# StepperDriverV2.net
KiCad netlist of a schematic drawn in Altium Designer
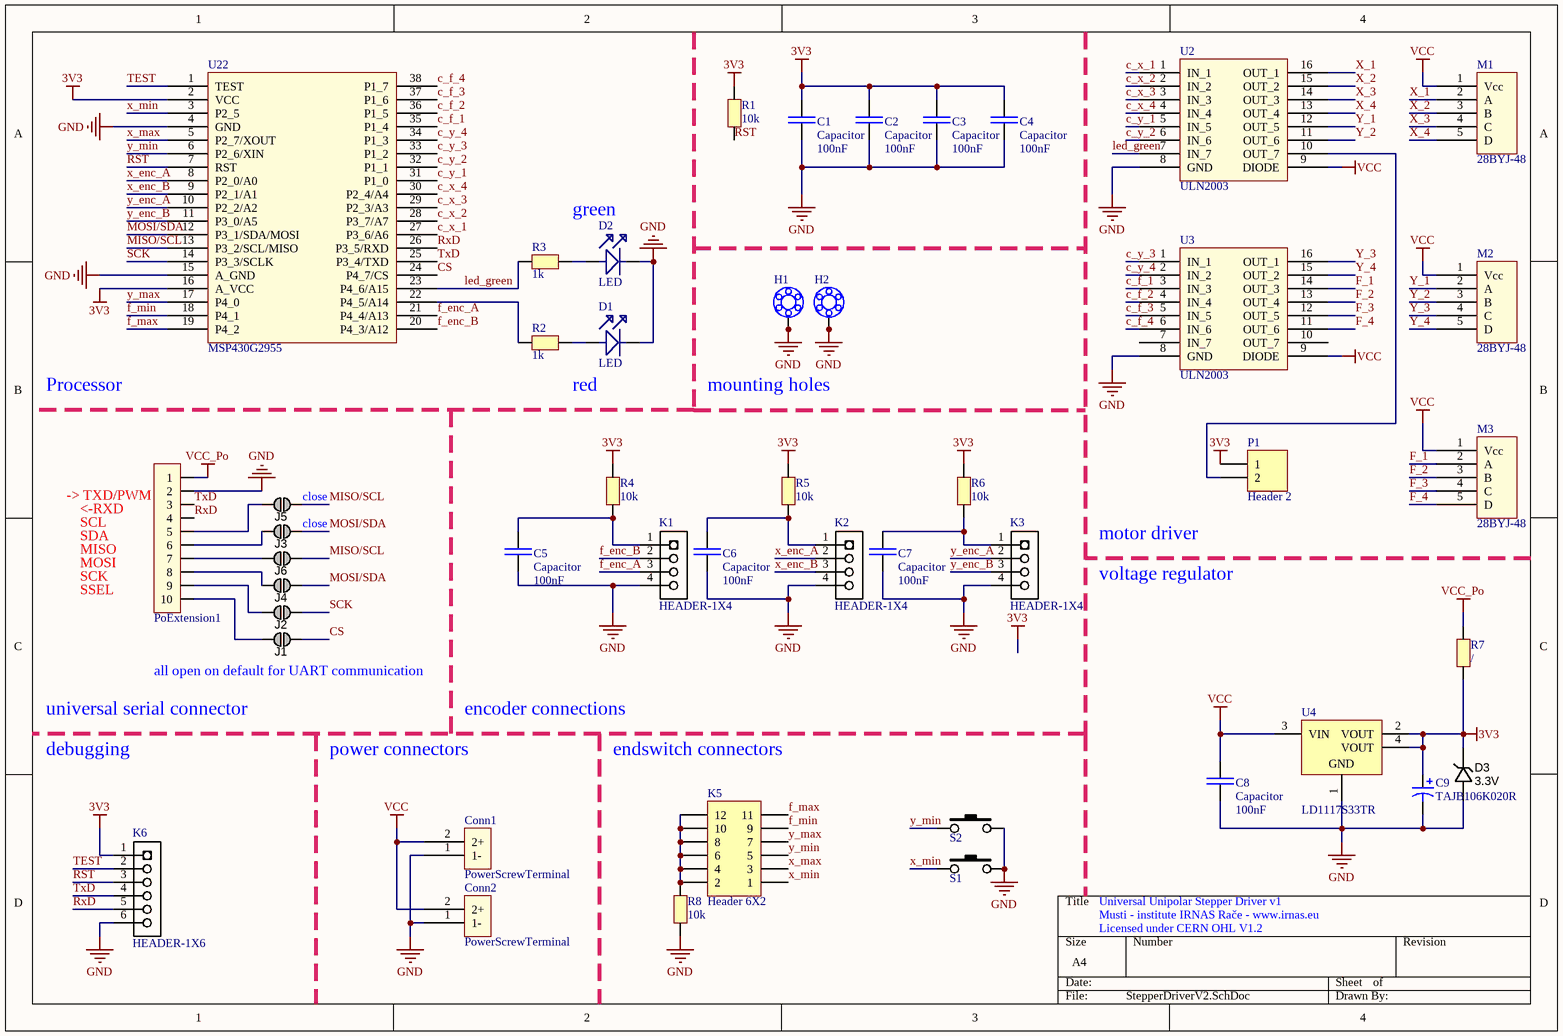
[diagram p0: StepperDriverV2.SchDoc]

(export (version "E")
  (design (tool "Eeschema 10.0.6"))
  (components
    (comp (ref "C1")
      (value "Capacitor")
      (footprint "0603")
      (description "General capacitor")
      (fields (field (name "ALTIUM_VALUE") "100nF"))
      (libsource (lib "GeneralComponents") (part "Capacitor"))
    )
    (comp (ref "C2")
      (value "Capacitor")
      (footprint "0603")
      (description "General capacitor")
      (fields (field (name "ALTIUM_VALUE") "100nF"))
      (libsource (lib "GeneralComponents") (part "Capacitor"))
    )
    (comp (ref "C3")
      (value "Capacitor")
      (footprint "0603")
      (description "General capacitor")
      (fields (field (name "ALTIUM_VALUE") "100nF"))
      (libsource (lib "GeneralComponents") (part "Capacitor"))
    )
    (comp (ref "C4")
      (value "Capacitor")
      (footprint "0603")
      (description "General capacitor")
      (fields (field (name "ALTIUM_VALUE") "100nF"))
      (libsource (lib "GeneralComponents") (part "Capacitor"))
    )
    (comp (ref "C5")
      (value "Capacitor")
      (footprint "0603")
      (description "General capacitor")
      (fields (field (name "ALTIUM_VALUE") "100nF"))
      (libsource (lib "GeneralComponents") (part "Capacitor"))
    )
    (comp (ref "C6")
      (value "Capacitor")
      (footprint "0603")
      (description "General capacitor")
      (fields (field (name "ALTIUM_VALUE") "100nF"))
      (libsource (lib "GeneralComponents") (part "Capacitor"))
    )
    (comp (ref "C7")
      (value "Capacitor")
      (footprint "0603")
      (description "General capacitor")
      (fields (field (name "ALTIUM_VALUE") "100nF"))
      (libsource (lib "GeneralComponents") (part "Capacitor"))
    )
    (comp (ref "C8")
      (value "Capacitor")
      (footprint "0603")
      (description "General capacitor")
      (fields (field (name "ALTIUM_VALUE") "100nF"))
      (libsource (lib "GeneralComponents") (part "Capacitor"))
    )
    (comp (ref "C9")
      (value "TAJB106K020R")
      (footprint "AVX-CAPC3528_V")
      (description "Capacitor, Tantalum, 10uF 10% 20V MCCT-B (3528)")
      (fields (field (name "MANUFACTURER") "AVX") (field (name "TOLERANCE") "10%"))
      (libsource (lib "Altium Content Vault") (part "CMP-0279-00001-1"))
    )
    (comp (ref "Conn1")
      (value "PowerScrewTerminal")
      (footprint "MKDSN 2,5/ 2-5,08 and powercon")
      (libsource (lib "GeneralComponents") (part "PowerScrewTerminal"))
    )
    (comp (ref "Conn2")
      (value "PowerScrewTerminal")
      (footprint "MKDSN 2,5/ 2-5,08 and powercon")
      (libsource (lib "GeneralComponents") (part "PowerScrewTerminal"))
    )
    (comp (ref "D1")
      (value "LED")
      (footprint "RESC2012X06N")
      (description "LED diode")
      (libsource (lib "GeneralComponents") (part "LED"))
    )
    (comp (ref "D2")
      (value "LED")
      (footprint "RESC2012X06N")
      (description "LED diode")
      (libsource (lib "GeneralComponents") (part "LED"))
    )
    (comp (ref "D3")
      (value "3.3V")
      (footprint "SOD323")
      (description "Diode Zener SMD 3.3V 200mW SOD-323")
      (fields (field (name "TOLERANCE") "±3%"))
      (libsource (lib "Misc") (part "DIODE_ZENER_3V3_SOD323"))
    )
    (comp (ref "H1")
      (value "M")
      (footprint "MOUNTING")
      (description "MOUNTING HOLE - NON INSTALLABLE")
      (libsource (lib "vh_altium_library") (part "MOUNTING"))
    )
    (comp (ref "H2")
      (value "M")
      (footprint "MOUNTING")
      (description "MOUNTING HOLE - NON INSTALLABLE")
      (libsource (lib "vh_altium_library") (part "MOUNTING"))
    )
    (comp (ref "J1")
      (value "Jumper")
      (footprint "JUMP1")
      (description "SMD jumper")
      (libsource (lib "Misc") (part "JUMP1"))
    )
    (comp (ref "J2")
      (value "Jumper")
      (footprint "JUMP1")
      (description "SMD jumper")
      (libsource (lib "Misc") (part "JUMP1"))
    )
    (comp (ref "J3")
      (value "Jumper")
      (footprint "JUMP1")
      (description "SMD jumper")
      (libsource (lib "Misc") (part "JUMP1"))
    )
    (comp (ref "J4")
      (value "Jumper")
      (footprint "JUMP1")
      (description "SMD jumper")
      (libsource (lib "Misc") (part "JUMP1"))
    )
    (comp (ref "J5")
      (value "Jumper")
      (footprint "JUMP1")
      (description "SMD jumper")
      (libsource (lib "Misc") (part "JUMP1"))
    )
    (comp (ref "J6")
      (value "Jumper")
      (footprint "JUMP1")
      (description "SMD jumper")
      (libsource (lib "Misc") (part "JUMP1"))
    )
    (comp (ref "K1")
      (value "HEADER-1X4")
      (footprint "HEADER-1X4")
      (libsource (lib "vh_altium_library") (part "HEADER-1X4"))
    )
    (comp (ref "K2")
      (value "HEADER-1X4")
      (footprint "HEADER-1X4")
      (libsource (lib "vh_altium_library") (part "HEADER-1X4"))
    )
    (comp (ref "K3")
      (value "HEADER-1X4")
      (footprint "HEADER-1X4")
      (libsource (lib "vh_altium_library") (part "HEADER-1X4"))
    )
    (comp (ref "K5")
      (value "Header 6X2")
      (footprint "HDR2X6")
      (description "Header, 6-Pin, Dual row")
      (fields (field (name "PUBLISHER") "Altium Limited"))
      (libsource (lib "Miscellaneous Connectors") (part "Header 6X2"))
    )
    (comp (ref "K6")
      (value "HEADER-1X6")
      (footprint "HEADER-1X6")
      (libsource (lib "vh_altium_library") (part "HEADER-1X6"))
    )
    (comp (ref "M1")
      (value "28BYJ-48")
      (footprint "XHP-5")
      (description "Stepper motor")
      (libsource (lib "GeneralComponents") (part "28BYJ-48"))
    )
    (comp (ref "M2")
      (value "28BYJ-48")
      (footprint "XHP-5")
      (description "Stepper motor")
      (libsource (lib "GeneralComponents") (part "28BYJ-48"))
    )
    (comp (ref "M3")
      (value "28BYJ-48")
      (footprint "XHP-5")
      (description "Stepper motor")
      (libsource (lib "GeneralComponents") (part "28BYJ-48"))
    )
    (comp (ref "P1")
      (value "Header 2")
      (footprint "HDR1X2")
      (description "Header, 2-Pin")
      (fields (field (name "PUBLISHER") "Altium Limited"))
      (libsource (lib "Miscellaneous Connectors") (part "Header 2"))
    )
    (comp (ref "PoExtension1")
      (value "~")
      (footprint "BorisMicroMatch:8-188275-0")
      (description "Micro-Match female PCB connector 10 Positions THT")
      (libsource (lib "BorisMicroMatch") (part "1-215079-0"))
    )
    (comp (ref "R1")
      (value "10k")
      (footprint "0603")
      (description "Resistor 0805 smd")
      (libsource (lib "GeneralComponents") (part "Resistor"))
    )
    (comp (ref "R2")
      (value "1k")
      (footprint "0603")
      (description "Resistor 0805 smd")
      (libsource (lib "") (part "Resistor_1"))
    )
    (comp (ref "R3")
      (value "1k")
      (footprint "0603")
      (description "Resistor 0805 smd")
      (libsource (lib "") (part "Resistor_1"))
    )
    (comp (ref "R4")
      (value "10k")
      (footprint "0603")
      (description "Resistor 0805 smd")
      (libsource (lib "GeneralComponents") (part "Resistor"))
    )
    (comp (ref "R5")
      (value "10k")
      (footprint "0603")
      (description "Resistor 0805 smd")
      (libsource (lib "GeneralComponents") (part "Resistor"))
    )
    (comp (ref "R6")
      (value "10k")
      (footprint "0603")
      (description "Resistor 0805 smd")
      (libsource (lib "GeneralComponents") (part "Resistor"))
    )
    (comp (ref "R7")
      (value "/")
      (footprint "0603")
      (description "Resistor 0805 smd")
      (libsource (lib "GeneralComponents") (part "Resistor"))
    )
    (comp (ref "R8")
      (value "10k")
      (footprint "0603")
      (description "Resistor 0805 smd")
      (libsource (lib "") (part "Resistor_2"))
    )
    (comp (ref "S1")
      (value "SW_THT_ANGLE")
      (footprint "TACT_Angle")
      (libsource (lib "Misc") (part "SW_THT_ANGLE"))
    )
    (comp (ref "S2")
      (value "SW_THT_ANGLE")
      (footprint "TACT_Angle")
      (libsource (lib "Misc") (part "SW_THT_ANGLE"))
    )
    (comp (ref "U2")
      (value "ULN2003")
      (footprint "SO-16 narrow")
      (description "Darlington array")
      (libsource (lib "GeneralComponents") (part "ULN2003"))
    )
    (comp (ref "U3")
      (value "ULN2003")
      (footprint "SO-16 narrow")
      (description "Darlington array")
      (libsource (lib "GeneralComponents") (part "ULN2003"))
    )
    (comp (ref "U4")
      (value "LD1117S33TR")
      (footprint "SOT-223_L")
      (description "Fixed Low Drop Positive Voltage Regulator, 3.3V, 4-Pin SOT-223, Tape and Reel")
      (libsource (lib "Altium Content Vault") (part "PM-REG-LD1117-SOT4"))
    )
    (comp (ref "U22")
      (value "MSP430G2955")
      (footprint "R-PDSO-G38")
      (libsource (lib "MSP430") (part "MSP430G2955"))
    )
  )
  (nets
    (net (code "1") (name "/CS") (class "Default")
      (node (ref "J1") (pin "2") (pintype "passive"))
      (node (ref "U22") (pin "24") (pinfunction "P4_7/CS_24") (pintype "passive"))
    )
    (net (code "2") (name "/F_1") (class "Default")
      (node (ref "M3") (pin "2") (pinfunction "A_2") (pintype "passive"))
      (node (ref "U3") (pin "14") (pinfunction "OUT_3_14") (pintype "passive"))
    )
    (net (code "3") (name "/F_2") (class "Default")
      (node (ref "M3") (pin "3") (pinfunction "B_3") (pintype "passive"))
      (node (ref "U3") (pin "13") (pinfunction "OUT_4_13") (pintype "passive"))
    )
    (net (code "4") (name "/F_3") (class "Default")
      (node (ref "M3") (pin "4") (pinfunction "C_4") (pintype "passive"))
      (node (ref "U3") (pin "12") (pinfunction "OUT_5_12") (pintype "passive"))
    )
    (net (code "5") (name "/F_4") (class "Default")
      (node (ref "M3") (pin "5") (pinfunction "D_5") (pintype "passive"))
      (node (ref "U3") (pin "11") (pinfunction "OUT_6_11") (pintype "passive"))
    )
    (net (code "6") (name "/MISO{slash}SCL") (class "Default")
      (node (ref "J5") (pin "1") (pintype "passive"))
      (node (ref "J6") (pin "1") (pintype "passive"))
      (node (ref "U22") (pin "13") (pinfunction "P3_2/SCL/MISO_13") (pintype "passive"))
    )
    (net (code "7") (name "/MOSI{slash}SDA") (class "Default")
      (node (ref "J3") (pin "1") (pintype "passive"))
      (node (ref "J4") (pin "1") (pintype "passive"))
      (node (ref "U22") (pin "12") (pinfunction "P3_1/SDA/MOSI_12") (pintype "passive"))
    )
    (net (code "8") (name "/RST") (class "Default")
      (node (ref "K6") (pin "3") (pintype "passive"))
      (node (ref "R1") (pin "1") (pinfunction "1_1") (pintype "passive"))
      (node (ref "U22") (pin "7") (pinfunction "RST_7") (pintype "passive"))
    )
    (net (code "9") (name "/RxD") (class "Default")
      (node (ref "K6") (pin "5") (pintype "passive"))
      (node (ref "PoExtension1") (pin "4") (pinfunction "4_4") (pintype "passive"))
      (node (ref "U22") (pin "26") (pinfunction "P3_5/RXD_26") (pintype "passive"))
    )
    (net (code "10") (name "/SCK") (class "Default")
      (node (ref "J2") (pin "2") (pintype "passive"))
      (node (ref "U22") (pin "14") (pinfunction "P3_3/SCLK_14") (pintype "passive"))
    )
    (net (code "11") (name "/TEST") (class "Default")
      (node (ref "K6") (pin "2") (pintype "passive"))
      (node (ref "U22") (pin "1") (pinfunction "TEST_1") (pintype "passive"))
    )
    (net (code "12") (name "/TxD") (class "Default")
      (node (ref "K6") (pin "4") (pintype "passive"))
      (node (ref "PoExtension1") (pin "3") (pinfunction "3_3") (pintype "passive"))
      (node (ref "U22") (pin "25") (pinfunction "P3_4/TXD_25") (pintype "passive"))
    )
    (net (code "13") (name "/X_1") (class "Default")
      (node (ref "M1") (pin "2") (pinfunction "A_2") (pintype "passive"))
      (node (ref "U2") (pin "16") (pinfunction "OUT_1_16") (pintype "passive"))
    )
    (net (code "14") (name "/X_2") (class "Default")
      (node (ref "M1") (pin "3") (pinfunction "B_3") (pintype "passive"))
      (node (ref "U2") (pin "15") (pinfunction "OUT_2_15") (pintype "passive"))
    )
    (net (code "15") (name "/X_3") (class "Default")
      (node (ref "M1") (pin "4") (pinfunction "C_4") (pintype "passive"))
      (node (ref "U2") (pin "14") (pinfunction "OUT_3_14") (pintype "passive"))
    )
    (net (code "16") (name "/X_4") (class "Default")
      (node (ref "M1") (pin "5") (pinfunction "D_5") (pintype "passive"))
      (node (ref "U2") (pin "13") (pinfunction "OUT_4_13") (pintype "passive"))
    )
    (net (code "17") (name "/Y_1") (class "Default")
      (node (ref "M2") (pin "2") (pinfunction "A_2") (pintype "passive"))
      (node (ref "U2") (pin "12") (pinfunction "OUT_5_12") (pintype "passive"))
    )
    (net (code "18") (name "/Y_2") (class "Default")
      (node (ref "M2") (pin "3") (pinfunction "B_3") (pintype "passive"))
      (node (ref "U2") (pin "11") (pinfunction "OUT_6_11") (pintype "passive"))
    )
    (net (code "19") (name "/Y_3") (class "Default")
      (node (ref "M2") (pin "4") (pinfunction "C_4") (pintype "passive"))
      (node (ref "U3") (pin "16") (pinfunction "OUT_1_16") (pintype "passive"))
    )
    (net (code "20") (name "/Y_4") (class "Default")
      (node (ref "M2") (pin "5") (pinfunction "D_5") (pintype "passive"))
      (node (ref "U3") (pin "15") (pinfunction "OUT_2_15") (pintype "passive"))
    )
    (net (code "21") (name "/c_f_1") (class "Default")
      (node (ref "U22") (pin "35") (pinfunction "P1_4_35") (pintype "passive"))
      (node (ref "U3") (pin "3") (pinfunction "IN_3_3") (pintype "passive"))
    )
    (net (code "22") (name "/c_f_2") (class "Default")
      (node (ref "U22") (pin "36") (pinfunction "P1_5_36") (pintype "passive"))
      (node (ref "U3") (pin "4") (pinfunction "IN_4_4") (pintype "passive"))
    )
    (net (code "23") (name "/c_f_3") (class "Default")
      (node (ref "U22") (pin "37") (pinfunction "P1_6_37") (pintype "passive"))
      (node (ref "U3") (pin "5") (pinfunction "IN_5_5") (pintype "passive"))
    )
    (net (code "24") (name "/c_f_4") (class "Default")
      (node (ref "U22") (pin "38") (pinfunction "P1_7_38") (pintype "passive"))
      (node (ref "U3") (pin "6") (pinfunction "IN_6_6") (pintype "passive"))
    )
    (net (code "25") (name "/c_x_1") (class "Default")
      (node (ref "U2") (pin "1") (pinfunction "IN_1_1") (pintype "passive"))
      (node (ref "U22") (pin "27") (pinfunction "P3_6/A6_27") (pintype "passive"))
    )
    (net (code "26") (name "/c_x_2") (class "Default")
      (node (ref "U2") (pin "2") (pinfunction "IN_2_2") (pintype "passive"))
      (node (ref "U22") (pin "28") (pinfunction "P3_7/A7_28") (pintype "passive"))
    )
    (net (code "27") (name "/c_x_3") (class "Default")
      (node (ref "U2") (pin "3") (pinfunction "IN_3_3") (pintype "passive"))
      (node (ref "U22") (pin "29") (pinfunction "P2_3/A3_29") (pintype "passive"))
    )
    (net (code "28") (name "/c_x_4") (class "Default")
      (node (ref "U2") (pin "4") (pinfunction "IN_4_4") (pintype "passive"))
      (node (ref "U22") (pin "30") (pinfunction "P2_4/A4_30") (pintype "passive"))
    )
    (net (code "29") (name "/c_y_1") (class "Default")
      (node (ref "U2") (pin "5") (pinfunction "IN_5_5") (pintype "passive"))
      (node (ref "U22") (pin "31") (pinfunction "P1_0_31") (pintype "passive"))
    )
    (net (code "30") (name "/c_y_2") (class "Default")
      (node (ref "U2") (pin "6") (pinfunction "IN_6_6") (pintype "passive"))
      (node (ref "U22") (pin "32") (pinfunction "P1_1_32") (pintype "passive"))
    )
    (net (code "31") (name "/c_y_3") (class "Default")
      (node (ref "U22") (pin "33") (pinfunction "P1_2_33") (pintype "passive"))
      (node (ref "U3") (pin "1") (pinfunction "IN_1_1") (pintype "passive"))
    )
    (net (code "32") (name "/c_y_4") (class "Default")
      (node (ref "U22") (pin "34") (pinfunction "P1_3_34") (pintype "passive"))
      (node (ref "U3") (pin "2") (pinfunction "IN_2_2") (pintype "passive"))
    )
    (net (code "33") (name "/f_enc_A") (class "Default")
      (node (ref "K1") (pin "3") (pintype "passive"))
      (node (ref "U22") (pin "21") (pinfunction "P4_4/A13_21") (pintype "passive"))
    )
    (net (code "34") (name "/f_enc_B") (class "Default")
      (node (ref "K1") (pin "2") (pintype "passive"))
      (node (ref "U22") (pin "20") (pinfunction "P4_3/A12_20") (pintype "passive"))
    )
    (net (code "35") (name "/f_max") (class "Default")
      (node (ref "K5") (pin "11") (pinfunction "11_11") (pintype "passive"))
      (node (ref "U22") (pin "19") (pinfunction "P4_2_19") (pintype "passive"))
    )
    (net (code "36") (name "/f_min") (class "Default")
      (node (ref "K5") (pin "9") (pinfunction "9_9") (pintype "passive"))
      (node (ref "U22") (pin "18") (pinfunction "P4_1_18") (pintype "passive"))
    )
    (net (code "37") (name "/led_green") (class "Default")
      (node (ref "R3") (pin "2") (pinfunction "2_2") (pintype "passive"))
      (node (ref "U2") (pin "7") (pinfunction "IN_7_7") (pintype "passive"))
      (node (ref "U22") (pin "23") (pinfunction "P4_6/A15_23") (pintype "passive"))
    )
    (net (code "38") (name "/x_enc_A") (class "Default")
      (node (ref "K2") (pin "2") (pintype "passive"))
      (node (ref "U22") (pin "8") (pinfunction "P2_0/A0_8") (pintype "passive"))
    )
    (net (code "39") (name "/x_enc_B") (class "Default")
      (node (ref "K2") (pin "3") (pintype "passive"))
      (node (ref "U22") (pin "9") (pinfunction "P2_1/A1_9") (pintype "passive"))
    )
    (net (code "40") (name "/x_max") (class "Default")
      (node (ref "K5") (pin "3") (pinfunction "3_3") (pintype "passive"))
      (node (ref "U22") (pin "5") (pinfunction "P2_7/XOUT_5") (pintype "passive"))
    )
    (net (code "41") (name "/x_min") (class "Default")
      (node (ref "K5") (pin "1") (pinfunction "1_1") (pintype "passive"))
      (node (ref "S1") (pin "1") (pintype "passive"))
      (node (ref "U22") (pin "3") (pinfunction "P2_5_3") (pintype "passive"))
    )
    (net (code "42") (name "/y_enc_A") (class "Default")
      (node (ref "K3") (pin "2") (pintype "passive"))
      (node (ref "U22") (pin "10") (pinfunction "P2_2/A2_10") (pintype "passive"))
    )
    (net (code "43") (name "/y_enc_B") (class "Default")
      (node (ref "K3") (pin "3") (pintype "passive"))
      (node (ref "U22") (pin "11") (pinfunction "P3_0/A5_11") (pintype "passive"))
    )
    (net (code "44") (name "/y_max") (class "Default")
      (node (ref "K5") (pin "7") (pinfunction "7_7") (pintype "passive"))
      (node (ref "U22") (pin "17") (pinfunction "P4_0_17") (pintype "passive"))
    )
    (net (code "45") (name "/y_min") (class "Default")
      (node (ref "K5") (pin "5") (pinfunction "5_5") (pintype "passive"))
      (node (ref "S2") (pin "1") (pintype "passive"))
      (node (ref "U22") (pin "6") (pinfunction "P2_6/XIN_6") (pintype "passive"))
    )
    (net (code "46") (name "3V3") (class "Default")
      (node (ref "C1") (pin "1") (pinfunction "1_1") (pintype "passive"))
      (node (ref "C2") (pin "1") (pinfunction "1_1") (pintype "passive"))
      (node (ref "C3") (pin "1") (pinfunction "1_1") (pintype "passive"))
      (node (ref "C4") (pin "1") (pinfunction "1_1") (pintype "passive"))
      (node (ref "C9") (pin "1") (pinfunction "1_1") (pintype "passive"))
      (node (ref "D3") (pin "K") (pinfunction "K_K") (pintype "passive"))
      (node (ref "K6") (pin "1") (pintype "passive"))
      (node (ref "P1") (pin "1") (pinfunction "1_1") (pintype "passive"))
      (node (ref "R1") (pin "2") (pinfunction "2_2") (pintype "passive"))
      (node (ref "R4") (pin "2") (pinfunction "2_2") (pintype "passive"))
      (node (ref "R5") (pin "2") (pinfunction "2_2") (pintype "passive"))
      (node (ref "R6") (pin "2") (pinfunction "2_2") (pintype "passive"))
      (node (ref "R7") (pin "1") (pinfunction "1_1") (pintype "passive"))
      (node (ref "U22") (pin "16") (pinfunction "A_VCC_16") (pintype "passive"))
      (node (ref "U22") (pin "2") (pinfunction "VCC_2") (pintype "passive"))
      (node (ref "U4") (pin "2") (pinfunction "VOUT_2") (pintype "power_in"))
      (node (ref "U4") (pin "4") (pinfunction "VOUT_4") (pintype "power_in"))
    )
    (net (code "47") (name "GND") (class "Default")
      (node (ref "C1") (pin "2") (pinfunction "2_2") (pintype "passive"))
      (node (ref "C2") (pin "2") (pinfunction "2_2") (pintype "passive"))
      (node (ref "C3") (pin "2") (pinfunction "2_2") (pintype "passive"))
      (node (ref "C4") (pin "2") (pinfunction "2_2") (pintype "passive"))
      (node (ref "C5") (pin "2") (pinfunction "2_2") (pintype "passive"))
      (node (ref "C6") (pin "2") (pinfunction "2_2") (pintype "passive"))
      (node (ref "C7") (pin "2") (pinfunction "2_2") (pintype "passive"))
      (node (ref "C8") (pin "2") (pinfunction "2_2") (pintype "passive"))
      (node (ref "C9") (pin "2") (pinfunction "2_2") (pintype "passive"))
      (node (ref "Conn1") (pin "1") (pinfunction "1-_1") (pintype "passive"))
      (node (ref "Conn2") (pin "1") (pinfunction "1-_1") (pintype "passive"))
      (node (ref "D1") (pin "2") (pinfunction "2_2") (pintype "passive"))
      (node (ref "D2") (pin "2") (pinfunction "2_2") (pintype "passive"))
      (node (ref "D3") (pin "A") (pinfunction "A_A") (pintype "passive"))
      (node (ref "H1") (pin "1") (pinfunction "1_1") (pintype "passive"))
      (node (ref "H1") (pin "2") (pinfunction "2_2") (pintype "passive"))
      (node (ref "H1") (pin "3") (pinfunction "3_3") (pintype "passive"))
      (node (ref "H1") (pin "4") (pinfunction "4_4") (pintype "passive"))
      (node (ref "H1") (pin "5") (pinfunction "5_5") (pintype "passive"))
      (node (ref "H1") (pin "6") (pinfunction "6_6") (pintype "passive"))
      (node (ref "H1") (pin "7") (pinfunction "7_7") (pintype "passive"))
      (node (ref "H2") (pin "1") (pinfunction "1_1") (pintype "passive"))
      (node (ref "H2") (pin "2") (pinfunction "2_2") (pintype "passive"))
      (node (ref "H2") (pin "3") (pinfunction "3_3") (pintype "passive"))
      (node (ref "H2") (pin "4") (pinfunction "4_4") (pintype "passive"))
      (node (ref "H2") (pin "5") (pinfunction "5_5") (pintype "passive"))
      (node (ref "H2") (pin "6") (pinfunction "6_6") (pintype "passive"))
      (node (ref "H2") (pin "7") (pinfunction "7_7") (pintype "passive"))
      (node (ref "K1") (pin "4") (pintype "passive"))
      (node (ref "K2") (pin "4") (pintype "passive"))
      (node (ref "K3") (pin "4") (pintype "passive"))
      (node (ref "K6") (pin "6") (pintype "passive"))
      (node (ref "PoExtension1") (pin "2") (pinfunction "2_2") (pintype "passive"))
      (node (ref "R8") (pin "2") (pinfunction "2_2") (pintype "passive"))
      (node (ref "S1") (pin "2") (pintype "passive"))
      (node (ref "S2") (pin "2") (pintype "passive"))
      (node (ref "U2") (pin "8") (pinfunction "GND_8") (pintype "passive"))
      (node (ref "U22") (pin "15") (pinfunction "A_GND_15") (pintype "passive"))
      (node (ref "U22") (pin "4") (pinfunction "GND_4") (pintype "passive"))
      (node (ref "U3") (pin "8") (pinfunction "GND_8") (pintype "passive"))
      (node (ref "U4") (pin "1") (pinfunction "GND_1") (pintype "power_in"))
    )
    (net (code "48") (name "Net-(C5-Pad1)") (class "Default")
      (node (ref "C5") (pin "1") (pinfunction "1_1") (pintype "passive"))
      (node (ref "K1") (pin "1") (pintype "passive"))
      (node (ref "R4") (pin "1") (pinfunction "1_1") (pintype "passive"))
    )
    (net (code "49") (name "Net-(C6-Pad1)") (class "Default")
      (node (ref "C6") (pin "1") (pinfunction "1_1") (pintype "passive"))
      (node (ref "K2") (pin "1") (pintype "passive"))
      (node (ref "R5") (pin "1") (pinfunction "1_1") (pintype "passive"))
    )
    (net (code "50") (name "Net-(C7-Pad1)") (class "Default")
      (node (ref "C7") (pin "1") (pinfunction "1_1") (pintype "passive"))
      (node (ref "K3") (pin "1") (pintype "passive"))
      (node (ref "R6") (pin "1") (pinfunction "1_1") (pintype "passive"))
    )
    (net (code "51") (name "Net-(D1-Pad1)") (class "Default")
      (node (ref "D1") (pin "1") (pinfunction "1_1") (pintype "passive"))
      (node (ref "R2") (pin "1") (pinfunction "1_1") (pintype "passive"))
    )
    (net (code "52") (name "Net-(D2-Pad1)") (class "Default")
      (node (ref "D2") (pin "1") (pinfunction "1_1") (pintype "passive"))
      (node (ref "R3") (pin "1") (pinfunction "1_1") (pintype "passive"))
    )
    (net (code "53") (name "Net-(J1-Pad1)") (class "Default")
      (node (ref "J1") (pin "1") (pintype "passive"))
      (node (ref "PoExtension1") (pin "10") (pinfunction "10_10") (pintype "passive"))
    )
    (net (code "54") (name "Net-(J2-Pad1)") (class "Default")
      (node (ref "J2") (pin "1") (pintype "passive"))
      (node (ref "PoExtension1") (pin "9") (pinfunction "9_9") (pintype "passive"))
    )
    (net (code "55") (name "Net-(J3-Pad2)") (class "Default")
      (node (ref "J3") (pin "2") (pintype "passive"))
      (node (ref "PoExtension1") (pin "6") (pinfunction "6_6") (pintype "passive"))
    )
    (net (code "56") (name "Net-(J4-Pad2)") (class "Default")
      (node (ref "J4") (pin "2") (pintype "passive"))
      (node (ref "PoExtension1") (pin "8") (pinfunction "8_8") (pintype "passive"))
    )
    (net (code "57") (name "Net-(J5-Pad2)") (class "Default")
      (node (ref "J5") (pin "2") (pintype "passive"))
      (node (ref "PoExtension1") (pin "5") (pinfunction "5_5") (pintype "passive"))
    )
    (net (code "58") (name "Net-(J6-Pad2)") (class "Default")
      (node (ref "J6") (pin "2") (pintype "passive"))
      (node (ref "PoExtension1") (pin "7") (pinfunction "7_7") (pintype "passive"))
    )
    (net (code "59") (name "Net-(K5-Pad10)") (class "Default")
      (node (ref "K5") (pin "10") (pinfunction "10_10") (pintype "passive"))
      (node (ref "K5") (pin "12") (pinfunction "12_12") (pintype "passive"))
      (node (ref "K5") (pin "2") (pinfunction "2_2") (pintype "passive"))
      (node (ref "K5") (pin "4") (pinfunction "4_4") (pintype "passive"))
      (node (ref "K5") (pin "6") (pinfunction "6_6") (pintype "passive"))
      (node (ref "K5") (pin "8") (pinfunction "8_8") (pintype "passive"))
      (node (ref "R8") (pin "1") (pinfunction "1_1") (pintype "passive"))
    )
    (net (code "60") (name "Net-(U2-OUT_7)") (class "Default")
      (node (ref "P1") (pin "2") (pinfunction "2_2") (pintype "passive"))
      (node (ref "U2") (pin "10") (pinfunction "OUT_7_10") (pintype "passive"))
    )
    (net (code "61") (name "Net-(U22-P4_5{slash}A14)") (class "Default")
      (node (ref "R2") (pin "2") (pinfunction "2_2") (pintype "passive"))
      (node (ref "U22") (pin "22") (pinfunction "P4_5/A14_22") (pintype "passive"))
    )
    (net (code "62") (name "VCC") (class "Default")
      (node (ref "C8") (pin "1") (pinfunction "1_1") (pintype "passive"))
      (node (ref "Conn1") (pin "2") (pinfunction "2+_2") (pintype "passive"))
      (node (ref "Conn2") (pin "2") (pinfunction "2+_2") (pintype "passive"))
      (node (ref "M1") (pin "1") (pinfunction "Vcc_1") (pintype "passive"))
      (node (ref "M2") (pin "1") (pinfunction "Vcc_1") (pintype "passive"))
      (node (ref "M3") (pin "1") (pinfunction "Vcc_1") (pintype "passive"))
      (node (ref "U2") (pin "9") (pinfunction "DIODE_9") (pintype "passive"))
      (node (ref "U3") (pin "9") (pinfunction "DIODE_9") (pintype "passive"))
      (node (ref "U4") (pin "3") (pinfunction "VIN_3") (pintype "power_in"))
    )
    (net (code "63") (name "VCC_Po") (class "Default")
      (node (ref "PoExtension1") (pin "1") (pinfunction "1_1") (pintype "passive"))
      (node (ref "R7") (pin "2") (pinfunction "2_2") (pintype "passive"))
    )
    (net (code "64") (name "unconnected-(U3-IN_7-Pad7)") (class "Default")
      (node (ref "U3") (pin "7") (pinfunction "IN_7_7") (pintype "passive"))
    )
    (net (code "65") (name "unconnected-(U3-OUT_7-Pad10)") (class "Default")
      (node (ref "U3") (pin "10") (pinfunction "OUT_7_10") (pintype "passive"))
    )
  )
)
